# motoko_ice_dragon.net
KiCad netlist of a schematic drawn in EAGLE
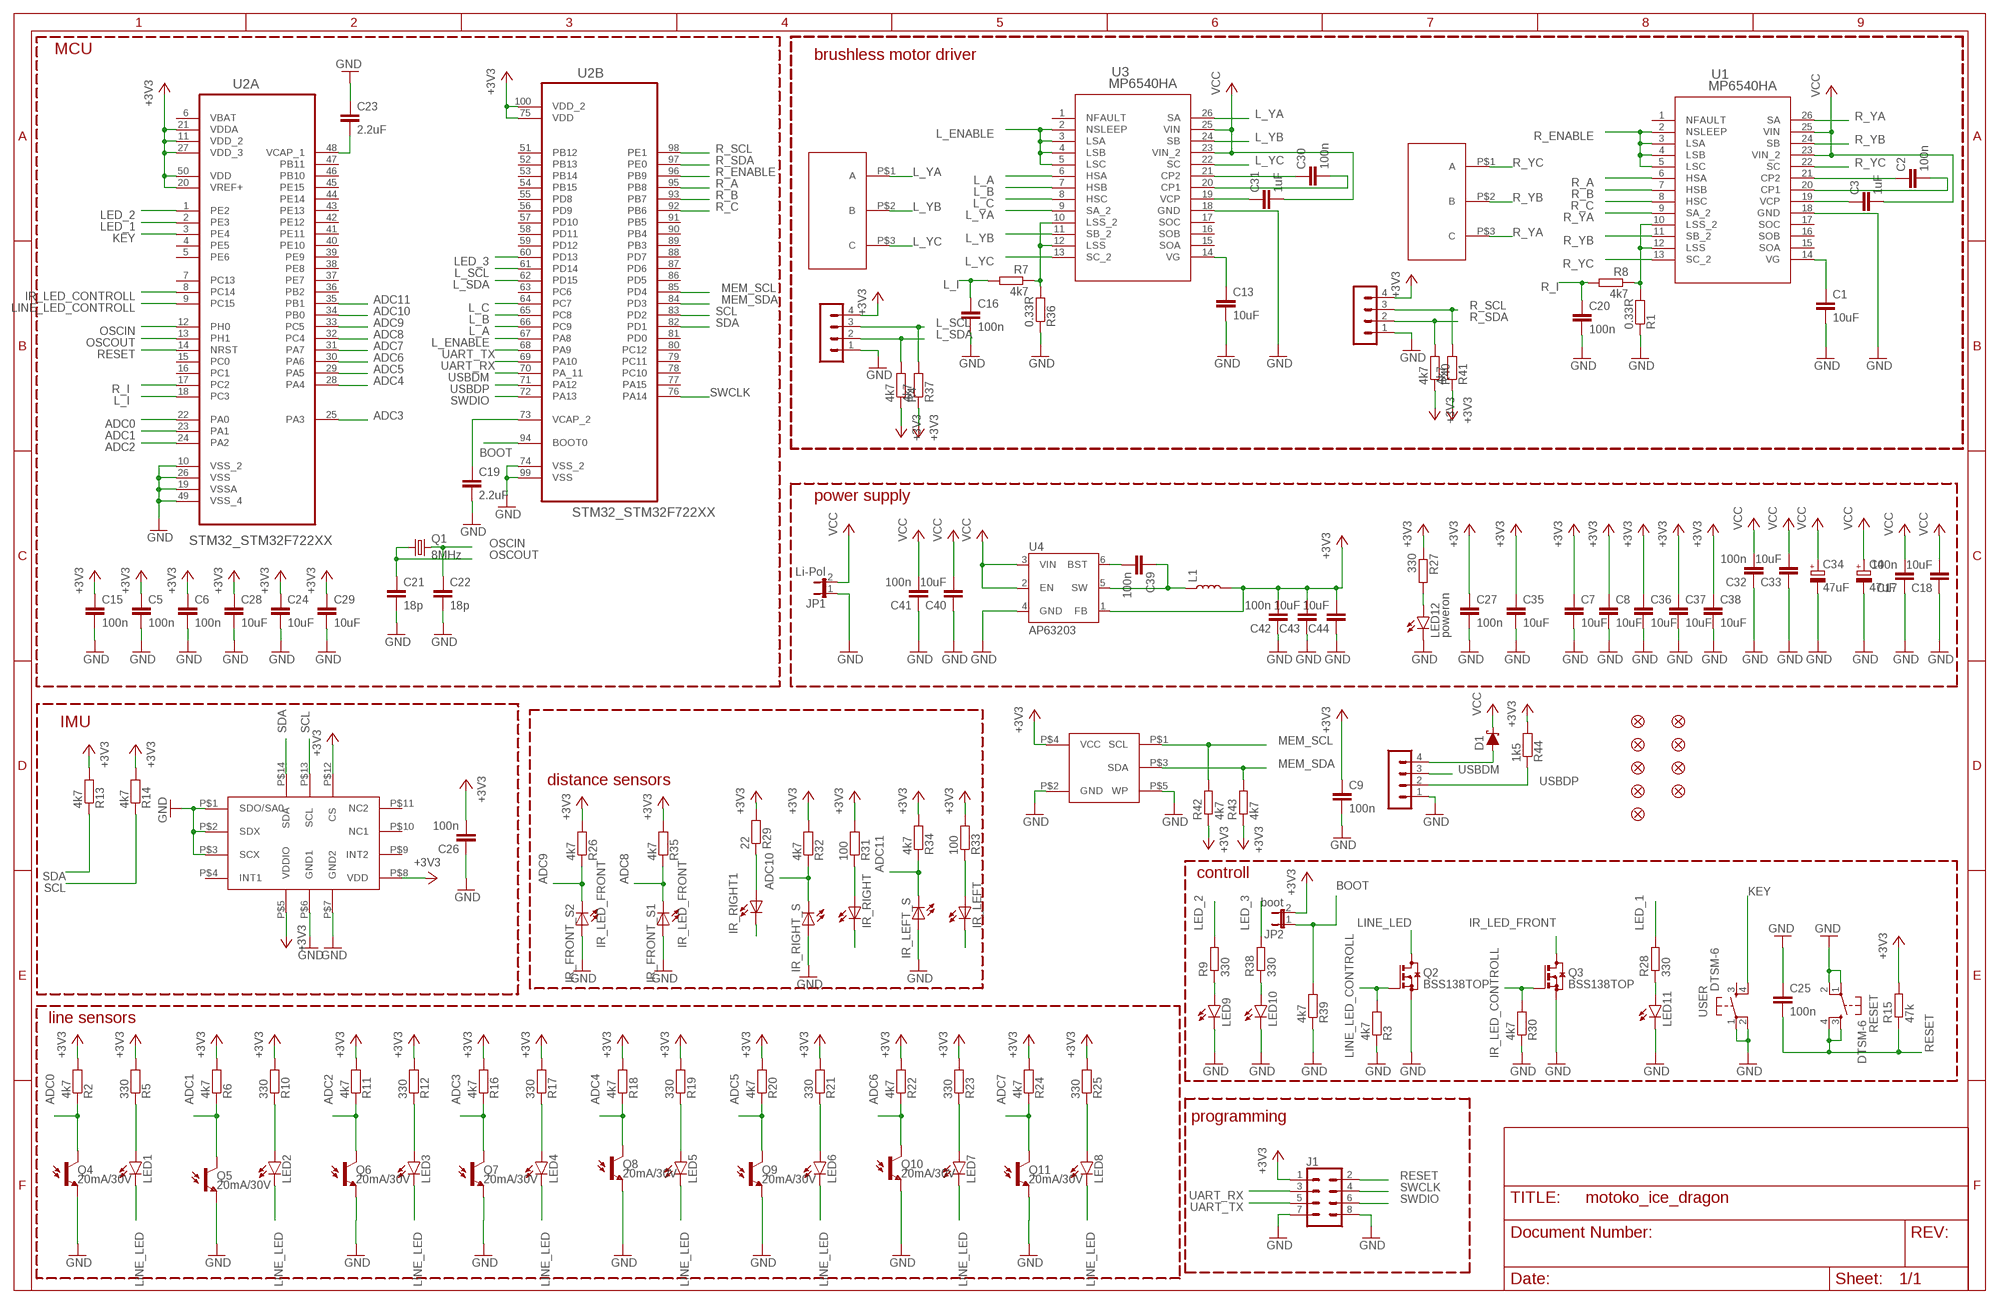
[diagram p0: schematic, sheet 1]

(export (version "E")
  (design (tool "Eeschema 10.0.6"))
  (components
    (comp (ref "C1")
      (value "10uF")
      (footprint "eagle-import:C0805")
      (libsource (lib "eagle-import") (part "C-EUC0805"))
    )
    (comp (ref "C2")
      (value "100n")
      (footprint "eagle-import:C0805")
      (libsource (lib "eagle-import") (part "C-EUC0805"))
    )
    (comp (ref "C3")
      (value "1uF")
      (footprint "eagle-import:C0805")
      (libsource (lib "eagle-import") (part "C-EUC0805"))
    )
    (comp (ref "C4")
      (value "47uF")
      (footprint "eagle-import:140CLH-1010")
      (libsource (lib "eagle-import") (part "CPOL-EU140CLH-1010"))
    )
    (comp (ref "C5")
      (value "100n")
      (footprint "eagle-import:C0805")
      (libsource (lib "eagle-import") (part "C-EUC0805"))
    )
    (comp (ref "C6")
      (value "100n")
      (footprint "eagle-import:C0805")
      (libsource (lib "eagle-import") (part "C-EUC0805"))
    )
    (comp (ref "C7")
      (value "10uF")
      (footprint "eagle-import:C0805")
      (libsource (lib "eagle-import") (part "C-EUC0805"))
    )
    (comp (ref "C8")
      (value "10uF")
      (footprint "eagle-import:C0805")
      (libsource (lib "eagle-import") (part "C-EUC0805"))
    )
    (comp (ref "C9")
      (value "100n")
      (footprint "eagle-import:C0805")
      (libsource (lib "eagle-import") (part "C-EUC0805"))
    )
    (comp (ref "C13")
      (value "10uF")
      (footprint "eagle-import:C0805")
      (libsource (lib "eagle-import") (part "C-EUC0805"))
    )
    (comp (ref "C15")
      (value "100n")
      (footprint "eagle-import:C0805")
      (libsource (lib "eagle-import") (part "C-EUC0805"))
    )
    (comp (ref "C16")
      (value "100n")
      (footprint "eagle-import:C0805")
      (libsource (lib "eagle-import") (part "C-EUC0805"))
    )
    (comp (ref "C17")
      (value "100n")
      (footprint "eagle-import:C0805")
      (libsource (lib "eagle-import") (part "C-EUC0805"))
    )
    (comp (ref "C18")
      (value "10uF")
      (footprint "eagle-import:C0805")
      (libsource (lib "eagle-import") (part "C-EUC0805"))
    )
    (comp (ref "C19")
      (value "2.2uF")
      (footprint "eagle-import:C0805")
      (libsource (lib "eagle-import") (part "C-EUC0805"))
    )
    (comp (ref "C20")
      (value "100n")
      (footprint "eagle-import:C0805")
      (libsource (lib "eagle-import") (part "C-EUC0805"))
    )
    (comp (ref "C21")
      (value "18p")
      (footprint "eagle-import:C0805")
      (libsource (lib "eagle-import") (part "C-EUC0805"))
    )
    (comp (ref "C22")
      (value "18p")
      (footprint "eagle-import:C0805")
      (libsource (lib "eagle-import") (part "C-EUC0805"))
    )
    (comp (ref "C23")
      (value "2.2uF")
      (footprint "eagle-import:C0805")
      (libsource (lib "eagle-import") (part "C-EUC0805"))
    )
    (comp (ref "C24")
      (value "10uF")
      (footprint "eagle-import:C0805")
      (libsource (lib "eagle-import") (part "C-EUC0805"))
    )
    (comp (ref "C25")
      (value "100n")
      (footprint "eagle-import:C0805")
      (libsource (lib "eagle-import") (part "C-EUC0805"))
    )
    (comp (ref "C26")
      (value "100n")
      (footprint "eagle-import:C0805")
      (libsource (lib "eagle-import") (part "C-EUC0805"))
    )
    (comp (ref "C27")
      (value "100n")
      (footprint "eagle-import:C0805")
      (libsource (lib "eagle-import") (part "C-EUC0805"))
    )
    (comp (ref "C28")
      (value "10uF")
      (footprint "eagle-import:C0805")
      (libsource (lib "eagle-import") (part "C-EUC0805"))
    )
    (comp (ref "C29")
      (value "10uF")
      (footprint "eagle-import:C0805")
      (libsource (lib "eagle-import") (part "C-EUC0805"))
    )
    (comp (ref "C30")
      (value "100n")
      (footprint "eagle-import:C0805")
      (libsource (lib "eagle-import") (part "C-EUC0805"))
    )
    (comp (ref "C31")
      (value "1uF")
      (footprint "eagle-import:C0805")
      (libsource (lib "eagle-import") (part "C-EUC0805"))
    )
    (comp (ref "C32")
      (value "100n")
      (footprint "eagle-import:C0805")
      (libsource (lib "eagle-import") (part "C-EUC0805"))
    )
    (comp (ref "C33")
      (value "10uF")
      (footprint "eagle-import:C0805")
      (libsource (lib "eagle-import") (part "C-EUC0805"))
    )
    (comp (ref "C34")
      (value "47uF")
      (footprint "eagle-import:140CLH-1010")
      (libsource (lib "eagle-import") (part "CPOL-EU140CLH-1010"))
    )
    (comp (ref "C35")
      (value "10uF")
      (footprint "eagle-import:C0805")
      (libsource (lib "eagle-import") (part "C-EUC0805"))
    )
    (comp (ref "C36")
      (value "10uF")
      (footprint "eagle-import:C0805")
      (libsource (lib "eagle-import") (part "C-EUC0805"))
    )
    (comp (ref "C37")
      (value "10uF")
      (footprint "eagle-import:C0805")
      (libsource (lib "eagle-import") (part "C-EUC0805"))
    )
    (comp (ref "C38")
      (value "10uF")
      (footprint "eagle-import:C0805")
      (libsource (lib "eagle-import") (part "C-EUC0805"))
    )
    (comp (ref "C39")
      (value "100n")
      (footprint "eagle-import:C0805")
      (libsource (lib "eagle-import") (part "C-EUC0805"))
    )
    (comp (ref "C40")
      (value "10uF")
      (footprint "eagle-import:C0805")
      (libsource (lib "eagle-import") (part "C-EUC0805"))
    )
    (comp (ref "C41")
      (value "100n")
      (footprint "eagle-import:C0805")
      (libsource (lib "eagle-import") (part "C-EUC0805"))
    )
    (comp (ref "C42")
      (value "100n")
      (footprint "eagle-import:C0805")
      (libsource (lib "eagle-import") (part "C-EUC0805"))
    )
    (comp (ref "C43")
      (value "10uF")
      (footprint "eagle-import:C0805")
      (libsource (lib "eagle-import") (part "C-EUC0805"))
    )
    (comp (ref "C44")
      (value "10uF")
      (footprint "eagle-import:C0805")
      (libsource (lib "eagle-import") (part "C-EUC0805"))
    )
    (comp (ref "D1")
      (value "3A/40V/500mV")
      (footprint "eagle-import:SMA-DIODE")
      (libsource (lib "eagle-import") (part "DIODE-SCHOTTKY-B340A"))
    )
    (comp (ref "FD1")
      (value "FIDUCIAL1X2")
      (footprint "eagle-import:FIDUCIAL-1X2")
      (libsource (lib "eagle-import") (part "FIDUCIAL1X2"))
    )
    (comp (ref "FD2")
      (value "FIDUCIAL1X2")
      (footprint "eagle-import:FIDUCIAL-1X2")
      (libsource (lib "eagle-import") (part "FIDUCIAL1X2"))
    )
    (comp (ref "FD3")
      (value "FIDUCIAL1X2")
      (footprint "eagle-import:FIDUCIAL-1X2")
      (libsource (lib "eagle-import") (part "FIDUCIAL1X2"))
    )
    (comp (ref "FD4")
      (value "FIDUCIAL1X2")
      (footprint "eagle-import:FIDUCIAL-1X2")
      (libsource (lib "eagle-import") (part "FIDUCIAL1X2"))
    )
    (comp (ref "FD5")
      (value "FIDUCIAL1X2")
      (footprint "eagle-import:FIDUCIAL-1X2")
      (libsource (lib "eagle-import") (part "FIDUCIAL1X2"))
    )
    (comp (ref "FD6")
      (value "FIDUCIAL1X2")
      (footprint "eagle-import:FIDUCIAL-1X2")
      (libsource (lib "eagle-import") (part "FIDUCIAL1X2"))
    )
    (comp (ref "FD7")
      (value "FIDUCIAL1X2")
      (footprint "eagle-import:FIDUCIAL-1X2")
      (libsource (lib "eagle-import") (part "FIDUCIAL1X2"))
    )
    (comp (ref "FD8")
      (value "FIDUCIAL1X2")
      (footprint "eagle-import:FIDUCIAL-1X2")
      (libsource (lib "eagle-import") (part "FIDUCIAL1X2"))
    )
    (comp (ref "FD9")
      (value "FIDUCIAL1X2")
      (footprint "eagle-import:FIDUCIAL-1X2")
      (libsource (lib "eagle-import") (part "FIDUCIAL1X2"))
    )
    (comp (ref "IR_FRONT_S1")
      (value "LED5MM")
      (footprint "eagle-import:LED5MM")
      (libsource (lib "eagle-import") (part "my_parts_LED5MM"))
    )
    (comp (ref "IR_FRONT_S2")
      (value "LED5MM")
      (footprint "eagle-import:LED5MM")
      (libsource (lib "eagle-import") (part "my_parts_LED5MM"))
    )
    (comp (ref "IR_LEFT")
      (value "LED5MM")
      (footprint "eagle-import:LED5MM")
      (libsource (lib "eagle-import") (part "my_parts_LED5MM"))
    )
    (comp (ref "IR_LEFT_S")
      (value "LED5MM")
      (footprint "eagle-import:LED5MM")
      (libsource (lib "eagle-import") (part "my_parts_LED5MM"))
    )
    (comp (ref "IR_RIGHT")
      (value "LED5MM")
      (footprint "eagle-import:LED5MM")
      (libsource (lib "eagle-import") (part "my_parts_LED5MM"))
    )
    (comp (ref "IR_RIGHT1")
      (value "LED5MM")
      (footprint "eagle-import:LED5MM")
      (libsource (lib "eagle-import") (part "my_parts_LED5MM"))
    )
    (comp (ref "IR_RIGHT_S")
      (value "LED5MM")
      (footprint "eagle-import:LED5MM")
      (libsource (lib "eagle-import") (part "my_parts_LED5MM"))
    )
    (comp (ref "J1")
      (value "CONN_04X2")
      (footprint "eagle-import:2X4")
      (libsource (lib "eagle-import") (part "CONN_04X2"))
    )
    (comp (ref "JP1")
      (value "Li-Pol")
      (footprint "eagle-import:JP1")
      (libsource (lib "eagle-import") (part "JP1E"))
    )
    (comp (ref "JP2")
      (value "boot")
      (footprint "eagle-import:JP1")
      (libsource (lib "eagle-import") (part "JP1E"))
    )
    (comp (ref "L1")
      (value "4.7uH, TYS50204R7N-10")
      (footprint "eagle-import:CR54")
      (libsource (lib "eagle-import") (part "INDUCTOR-CR54-3.3UH"))
    )
    (comp (ref "LED1")
      (value "LEDCHIPLED_1206")
      (footprint "eagle-import:CHIPLED_1206")
      (libsource (lib "eagle-import") (part "LEDCHIPLED_1206"))
    )
    (comp (ref "LED2")
      (value "LEDCHIPLED_1206")
      (footprint "eagle-import:CHIPLED_1206")
      (libsource (lib "eagle-import") (part "LEDCHIPLED_1206"))
    )
    (comp (ref "LED3")
      (value "LEDCHIPLED_1206")
      (footprint "eagle-import:CHIPLED_1206")
      (libsource (lib "eagle-import") (part "LEDCHIPLED_1206"))
    )
    (comp (ref "LED4")
      (value "LEDCHIPLED_1206")
      (footprint "eagle-import:CHIPLED_1206")
      (libsource (lib "eagle-import") (part "LEDCHIPLED_1206"))
    )
    (comp (ref "LED5")
      (value "LEDCHIPLED_1206")
      (footprint "eagle-import:CHIPLED_1206")
      (libsource (lib "eagle-import") (part "LEDCHIPLED_1206"))
    )
    (comp (ref "LED6")
      (value "LEDCHIPLED_1206")
      (footprint "eagle-import:CHIPLED_1206")
      (libsource (lib "eagle-import") (part "LEDCHIPLED_1206"))
    )
    (comp (ref "LED7")
      (value "LEDCHIPLED_1206")
      (footprint "eagle-import:CHIPLED_1206")
      (libsource (lib "eagle-import") (part "LEDCHIPLED_1206"))
    )
    (comp (ref "LED8")
      (value "LEDCHIPLED_1206")
      (footprint "eagle-import:CHIPLED_1206")
      (libsource (lib "eagle-import") (part "LEDCHIPLED_1206"))
    )
    (comp (ref "LED9")
      (value "LEDCHIPLED_1206")
      (footprint "eagle-import:CHIPLED_1206")
      (libsource (lib "eagle-import") (part "LEDCHIPLED_1206"))
    )
    (comp (ref "LED10")
      (value "LEDCHIPLED_1206")
      (footprint "eagle-import:CHIPLED_1206")
      (libsource (lib "eagle-import") (part "LEDCHIPLED_1206"))
    )
    (comp (ref "LED11")
      (value "LEDCHIPLED_1206")
      (footprint "eagle-import:CHIPLED_1206")
      (libsource (lib "eagle-import") (part "LEDCHIPLED_1206"))
    )
    (comp (ref "LED12")
      (value "poweron")
      (footprint "eagle-import:CHIPLED_1206")
      (libsource (lib "eagle-import") (part "LEDCHIPLED_1206"))
    )
    (comp (ref "L_ENCODER")
      (value "MA04-1")
      (footprint "eagle-import:MA04-1")
      (libsource (lib "eagle-import") (part "MA04-1"))
    )
    (comp (ref "L_ENCODER1")
      (value "MA04-1")
      (footprint "eagle-import:MA04-1")
      (libsource (lib "eagle-import") (part "MA04-1"))
    )
    (comp (ref "L_ENCODER2")
      (value "MA04-1")
      (footprint "eagle-import:MA04-1")
      (libsource (lib "eagle-import") (part "MA04-1"))
    )
    (comp (ref "Q1")
      (value "8MHz")
      (footprint "eagle-import:CTS406")
      (libsource (lib "eagle-import") (part "CRYSTALCTS406"))
    )
    (comp (ref "Q2")
      (value "BSS138TOP")
      (footprint "eagle-import:SOT23")
      (libsource (lib "eagle-import") (part "BSS138TOP"))
    )
    (comp (ref "Q3")
      (value "BSS138TOP")
      (footprint "eagle-import:SOT23")
      (libsource (lib "eagle-import") (part "BSS138TOP"))
    )
    (comp (ref "Q4")
      (value "20mA/30V")
      (footprint "eagle-import:PT17-21C-L41-TR8")
      (libsource (lib "eagle-import") (part "PHOTOTRANSISTORPT17-21C-L41-TR8"))
    )
    (comp (ref "Q5")
      (value "20mA/30V")
      (footprint "eagle-import:PT17-21C-L41-TR8")
      (libsource (lib "eagle-import") (part "PHOTOTRANSISTORPT17-21C-L41-TR8"))
    )
    (comp (ref "Q6")
      (value "20mA/30V")
      (footprint "eagle-import:PT17-21C-L41-TR8")
      (libsource (lib "eagle-import") (part "PHOTOTRANSISTORPT17-21C-L41-TR8"))
    )
    (comp (ref "Q7")
      (value "20mA/30V")
      (footprint "eagle-import:PT17-21C-L41-TR8")
      (libsource (lib "eagle-import") (part "PHOTOTRANSISTORPT17-21C-L41-TR8"))
    )
    (comp (ref "Q8")
      (value "20mA/30V")
      (footprint "eagle-import:PT17-21C-L41-TR8")
      (libsource (lib "eagle-import") (part "PHOTOTRANSISTORPT17-21C-L41-TR8"))
    )
    (comp (ref "Q9")
      (value "20mA/30V")
      (footprint "eagle-import:PT17-21C-L41-TR8")
      (libsource (lib "eagle-import") (part "PHOTOTRANSISTORPT17-21C-L41-TR8"))
    )
    (comp (ref "Q10")
      (value "20mA/30V")
      (footprint "eagle-import:PT17-21C-L41-TR8")
      (libsource (lib "eagle-import") (part "PHOTOTRANSISTORPT17-21C-L41-TR8"))
    )
    (comp (ref "Q11")
      (value "20mA/30V")
      (footprint "eagle-import:PT17-21C-L41-TR8")
      (libsource (lib "eagle-import") (part "PHOTOTRANSISTORPT17-21C-L41-TR8"))
    )
    (comp (ref "R1")
      (value "0.33R")
      (footprint "eagle-import:M1206")
      (libsource (lib "eagle-import") (part "R-EU_M1206"))
    )
    (comp (ref "R2")
      (value "4k7")
      (footprint "eagle-import:M0805")
      (libsource (lib "eagle-import") (part "resistor_348_R-EU_M0805"))
    )
    (comp (ref "R3")
      (value "4k7")
      (footprint "eagle-import:M0805")
      (libsource (lib "eagle-import") (part "resistor_348_R-EU_M0805"))
    )
    (comp (ref "R4")
      (value "4k7")
      (footprint "eagle-import:M0805")
      (libsource (lib "eagle-import") (part "resistor_348_R-EU_M0805"))
    )
    (comp (ref "R5")
      (value "330")
      (footprint "eagle-import:M0805")
      (libsource (lib "eagle-import") (part "resistor_348_R-EU_M0805"))
    )
    (comp (ref "R6")
      (value "4k7")
      (footprint "eagle-import:M0805")
      (libsource (lib "eagle-import") (part "resistor_348_R-EU_M0805"))
    )
    (comp (ref "R7")
      (value "4k7")
      (footprint "eagle-import:M0805")
      (libsource (lib "eagle-import") (part "resistor_348_R-EU_M0805"))
    )
    (comp (ref "R8")
      (value "4k7")
      (footprint "eagle-import:M0805")
      (libsource (lib "eagle-import") (part "resistor_348_R-EU_M0805"))
    )
    (comp (ref "R9")
      (value "330")
      (footprint "eagle-import:M0805")
      (libsource (lib "eagle-import") (part "resistor_348_R-EU_M0805"))
    )
    (comp (ref "R10")
      (value "330")
      (footprint "eagle-import:M0805")
      (libsource (lib "eagle-import") (part "resistor_348_R-EU_M0805"))
    )
    (comp (ref "R11")
      (value "4k7")
      (footprint "eagle-import:M0805")
      (libsource (lib "eagle-import") (part "resistor_348_R-EU_M0805"))
    )
    (comp (ref "R12")
      (value "330")
      (footprint "eagle-import:M0805")
      (libsource (lib "eagle-import") (part "resistor_348_R-EU_M0805"))
    )
    (comp (ref "R13")
      (value "4k7")
      (footprint "eagle-import:M0805")
      (libsource (lib "eagle-import") (part "resistor_348_R-EU_M0805"))
    )
    (comp (ref "R14")
      (value "4k7")
      (footprint "eagle-import:M0805")
      (libsource (lib "eagle-import") (part "resistor_348_R-EU_M0805"))
    )
    (comp (ref "R15")
      (value "47k")
      (footprint "eagle-import:M0805")
      (libsource (lib "eagle-import") (part "resistor_348_R-EU_M0805"))
    )
    (comp (ref "R16")
      (value "4k7")
      (footprint "eagle-import:M0805")
      (libsource (lib "eagle-import") (part "resistor_348_R-EU_M0805"))
    )
    (comp (ref "R17")
      (value "330")
      (footprint "eagle-import:M0805")
      (libsource (lib "eagle-import") (part "resistor_348_R-EU_M0805"))
    )
    (comp (ref "R18")
      (value "4k7")
      (footprint "eagle-import:M0805")
      (libsource (lib "eagle-import") (part "resistor_348_R-EU_M0805"))
    )
    (comp (ref "R19")
      (value "330")
      (footprint "eagle-import:M0805")
      (libsource (lib "eagle-import") (part "resistor_348_R-EU_M0805"))
    )
    (comp (ref "R20")
      (value "4k7")
      (footprint "eagle-import:M0805")
      (libsource (lib "eagle-import") (part "resistor_348_R-EU_M0805"))
    )
    (comp (ref "R21")
      (value "330")
      (footprint "eagle-import:M0805")
      (libsource (lib "eagle-import") (part "resistor_348_R-EU_M0805"))
    )
    (comp (ref "R22")
      (value "4k7")
      (footprint "eagle-import:M0805")
      (libsource (lib "eagle-import") (part "resistor_348_R-EU_M0805"))
    )
    (comp (ref "R23")
      (value "330")
      (footprint "eagle-import:M0805")
      (libsource (lib "eagle-import") (part "resistor_348_R-EU_M0805"))
    )
    (comp (ref "R24")
      (value "4k7")
      (footprint "eagle-import:M0805")
      (libsource (lib "eagle-import") (part "resistor_348_R-EU_M0805"))
    )
    (comp (ref "R25")
      (value "330")
      (footprint "eagle-import:M0805")
      (libsource (lib "eagle-import") (part "resistor_348_R-EU_M0805"))
    )
    (comp (ref "R26")
      (value "4k7")
      (footprint "eagle-import:M0805")
      (libsource (lib "eagle-import") (part "resistor_348_R-EU_M0805"))
    )
    (comp (ref "R27")
      (value "330")
      (footprint "eagle-import:M0805")
      (libsource (lib "eagle-import") (part "resistor_348_R-EU_M0805"))
    )
    (comp (ref "R28")
      (value "330")
      (footprint "eagle-import:M0805")
      (libsource (lib "eagle-import") (part "resistor_348_R-EU_M0805"))
    )
    (comp (ref "R29")
      (value "22")
      (footprint "eagle-import:M0805")
      (libsource (lib "eagle-import") (part "resistor_348_R-EU_M0805"))
    )
    (comp (ref "R30")
      (value "4k7")
      (footprint "eagle-import:M0805")
      (libsource (lib "eagle-import") (part "resistor_348_R-EU_M0805"))
    )
    (comp (ref "R31")
      (value "100")
      (footprint "eagle-import:M0805")
      (libsource (lib "eagle-import") (part "resistor_348_R-EU_M0805"))
    )
    (comp (ref "R32")
      (value "4k7")
      (footprint "eagle-import:M0805")
      (libsource (lib "eagle-import") (part "resistor_348_R-EU_M0805"))
    )
    (comp (ref "R33")
      (value "100")
      (footprint "eagle-import:M0805")
      (libsource (lib "eagle-import") (part "resistor_348_R-EU_M0805"))
    )
    (comp (ref "R34")
      (value "4k7")
      (footprint "eagle-import:M0805")
      (libsource (lib "eagle-import") (part "resistor_348_R-EU_M0805"))
    )
    (comp (ref "R35")
      (value "4k7")
      (footprint "eagle-import:M0805")
      (libsource (lib "eagle-import") (part "resistor_348_R-EU_M0805"))
    )
    (comp (ref "R36")
      (value "0.33R")
      (footprint "eagle-import:M1206")
      (libsource (lib "eagle-import") (part "R-EU_M1206"))
    )
    (comp (ref "R37")
      (value "4k7")
      (footprint "eagle-import:M0805")
      (libsource (lib "eagle-import") (part "resistor_348_R-EU_M0805"))
    )
    (comp (ref "R38")
      (value "330")
      (footprint "eagle-import:M0805")
      (libsource (lib "eagle-import") (part "resistor_348_R-EU_M0805"))
    )
    (comp (ref "R39")
      (value "4k7")
      (footprint "eagle-import:M0805")
      (libsource (lib "eagle-import") (part "resistor_348_R-EU_M0805"))
    )
    (comp (ref "R40")
      (value "4k7")
      (footprint "eagle-import:M0805")
      (libsource (lib "eagle-import") (part "resistor_348_R-EU_M0805"))
    )
    (comp (ref "R41")
      (value "4k7")
      (footprint "eagle-import:M0805")
      (libsource (lib "eagle-import") (part "resistor_348_R-EU_M0805"))
    )
    (comp (ref "R42")
      (value "4k7")
      (footprint "eagle-import:M0805")
      (libsource (lib "eagle-import") (part "R-EU_M0805"))
    )
    (comp (ref "R43")
      (value "4k7")
      (footprint "eagle-import:M0805")
      (libsource (lib "eagle-import") (part "R-EU_M0805"))
    )
    (comp (ref "R44")
      (value "1k5")
      (footprint "eagle-import:M0805")
      (libsource (lib "eagle-import") (part "resistor_348_R-EU_M0805"))
    )
    (comp (ref "RESET")
      (value "DTSM-6")
      (footprint "eagle-import:DTSM-6")
      (libsource (lib "eagle-import") (part "DTSM-6"))
    )
    (comp (ref "U$1")
      (value "BRUSHLESS_GIMBAL_MOTOR_WHEEL")
      (footprint "eagle-import:BRUSHLESS_GIMBAL_MOTOR_WHEEL")
      (libsource (lib "eagle-import") (part "BRUSHLESS_GIMBAL_MOTOR_WHEEL"))
    )
    (comp (ref "U$2")
      (value "BRUSHLESS_GIMBAL_MOTOR_WHEEL")
      (footprint "eagle-import:BRUSHLESS_GIMBAL_MOTOR_WHEEL")
      (libsource (lib "eagle-import") (part "BRUSHLESS_GIMBAL_MOTOR_WHEEL"))
    )
    (comp (ref "U$3")
      (value "LSM6DSM")
      (footprint "eagle-import:LGA14L")
      (libsource (lib "eagle-import") (part "LSM6DSM"))
    )
    (comp (ref "U$4")
      (value "24LC24_SOT23")
      (footprint "eagle-import:SOT23")
      (libsource (lib "eagle-import") (part "24LC24_SOT23"))
    )
    (comp (ref "U1")
      (value "MP6540HA")
      (footprint "eagle-import:QFN-5X5_MP6540HA_MNP")
      (fields (field (name "COPYRIGHT") "Copyright (C) 2018 Accelerated Designs. All rights reserved"))
      (libsource (lib "eagle-import") (part "MP6540HA"))
    )
    (comp (ref "U2")
      (value "STM32_STM32F722XX")
      (footprint "eagle-import:STM32_QFP50P1600X1600X160-100N")
      (fields (field (name "MPN") "STM32F407VET6"))
      (libsource (lib "eagle-import") (part "STM32_STM32F722XX"))
    )
    (comp (ref "U3")
      (value "MP6540HA")
      (footprint "eagle-import:QFN-5X5_MP6540HA_MNP")
      (fields (field (name "COPYRIGHT") "Copyright (C) 2018 Accelerated Designs. All rights reserved"))
      (libsource (lib "eagle-import") (part "MP6540HA"))
    )
    (comp (ref "U4")
      (value "AP63203")
      (footprint "eagle-import:SOT23-6")
      (libsource (lib "eagle-import") (part "AP63203"))
    )
    (comp (ref "USER")
      (value "DTSM-6")
      (footprint "eagle-import:DTSM-6")
      (libsource (lib "eagle-import") (part "DTSM-6"))
    )
  )
  (nets
    (net (code "1") (name "+3V3") (class "Default")
      (node (ref "C15") (pin "1") (pinfunction "1_1") (pintype "passive"))
      (node (ref "C24") (pin "1") (pinfunction "1_1") (pintype "passive"))
      (node (ref "C26") (pin "2") (pinfunction "2_2") (pintype "passive"))
      (node (ref "C27") (pin "1") (pinfunction "1_1") (pintype "passive"))
      (node (ref "C28") (pin "1") (pinfunction "1_1") (pintype "passive"))
      (node (ref "C29") (pin "1") (pinfunction "1_1") (pintype "passive"))
      (node (ref "C35") (pin "1") (pinfunction "1_1") (pintype "passive"))
      (node (ref "C36") (pin "1") (pinfunction "1_1") (pintype "passive"))
      (node (ref "C37") (pin "1") (pinfunction "1_1") (pintype "passive"))
      (node (ref "C38") (pin "1") (pinfunction "1_1") (pintype "passive"))
      (node (ref "C42") (pin "2") (pinfunction "2_2") (pintype "passive"))
      (node (ref "C43") (pin "2") (pinfunction "2_2") (pintype "passive"))
      (node (ref "C44") (pin "2") (pinfunction "2_2") (pintype "passive"))
      (node (ref "C5") (pin "1") (pinfunction "1_1") (pintype "passive"))
      (node (ref "C6") (pin "1") (pinfunction "1_1") (pintype "passive"))
      (node (ref "C7") (pin "1") (pinfunction "1_1") (pintype "passive"))
      (node (ref "C8") (pin "1") (pinfunction "1_1") (pintype "passive"))
      (node (ref "C9") (pin "1") (pinfunction "1_1") (pintype "passive"))
      (node (ref "J1") (pin "1") (pinfunction "1_1") (pintype "passive"))
      (node (ref "JP2") (pin "2") (pinfunction "2_2") (pintype "passive"))
      (node (ref "L1") (pin "P$2") (pinfunction "2_P$2") (pintype "passive"))
      (node (ref "L_ENCODER") (pin "4") (pinfunction "4_4") (pintype "passive"))
      (node (ref "L_ENCODER1") (pin "4") (pinfunction "4_4") (pintype "passive"))
      (node (ref "R10") (pin "2") (pinfunction "2_2") (pintype "passive"))
      (node (ref "R11") (pin "2") (pinfunction "2_2") (pintype "passive"))
      (node (ref "R12") (pin "2") (pinfunction "2_2") (pintype "passive"))
      (node (ref "R13") (pin "2") (pinfunction "2_2") (pintype "passive"))
      (node (ref "R14") (pin "2") (pinfunction "2_2") (pintype "passive"))
      (node (ref "R15") (pin "2") (pinfunction "2_2") (pintype "passive"))
      (node (ref "R16") (pin "2") (pinfunction "2_2") (pintype "passive"))
      (node (ref "R17") (pin "2") (pinfunction "2_2") (pintype "passive"))
      (node (ref "R18") (pin "2") (pinfunction "2_2") (pintype "passive"))
      (node (ref "R19") (pin "2") (pinfunction "2_2") (pintype "passive"))
      (node (ref "R2") (pin "2") (pinfunction "2_2") (pintype "passive"))
      (node (ref "R20") (pin "2") (pinfunction "2_2") (pintype "passive"))
      (node (ref "R21") (pin "2") (pinfunction "2_2") (pintype "passive"))
      (node (ref "R22") (pin "2") (pinfunction "2_2") (pintype "passive"))
      (node (ref "R23") (pin "2") (pinfunction "2_2") (pintype "passive"))
      (node (ref "R24") (pin "2") (pinfunction "2_2") (pintype "passive"))
      (node (ref "R25") (pin "2") (pinfunction "2_2") (pintype "passive"))
      (node (ref "R26") (pin "2") (pinfunction "2_2") (pintype "passive"))
      (node (ref "R27") (pin "1") (pinfunction "1_1") (pintype "passive"))
      (node (ref "R29") (pin "2") (pinfunction "2_2") (pintype "passive"))
      (node (ref "R31") (pin "2") (pinfunction "2_2") (pintype "passive"))
      (node (ref "R32") (pin "2") (pinfunction "2_2") (pintype "passive"))
      (node (ref "R33") (pin "2") (pinfunction "2_2") (pintype "passive"))
      (node (ref "R34") (pin "2") (pinfunction "2_2") (pintype "passive"))
      (node (ref "R35") (pin "2") (pinfunction "2_2") (pintype "passive"))
      (node (ref "R37") (pin "1") (pinfunction "1_1") (pintype "passive"))
      (node (ref "R4") (pin "1") (pinfunction "1_1") (pintype "passive"))
      (node (ref "R40") (pin "1") (pinfunction "1_1") (pintype "passive"))
      (node (ref "R41") (pin "1") (pinfunction "1_1") (pintype "passive"))
      (node (ref "R42") (pin "1") (pinfunction "1_1") (pintype "passive"))
      (node (ref "R43") (pin "1") (pinfunction "1_1") (pintype "passive"))
      (node (ref "R44") (pin "2") (pinfunction "2_2") (pintype "passive"))
      (node (ref "R5") (pin "2") (pinfunction "2_2") (pintype "passive"))
      (node (ref "R6") (pin "2") (pinfunction "2_2") (pintype "passive"))
      (node (ref "U$3") (pin "P$12") (pinfunction "CS_P$12") (pintype "bidirectional"))
      (node (ref "U$3") (pin "P$5") (pinfunction "VDDIO_P$5") (pintype "bidirectional"))
      (node (ref "U$3") (pin "P$8") (pinfunction "VDD_P$8") (pintype "bidirectional"))
      (node (ref "U$4") (pin "P$4") (pinfunction "VCC_P$4") (pintype "bidirectional"))
      (node (ref "U2") (pin "100") (pinfunction "VDD_2_100") (pintype "power_in"))
      (node (ref "U2") (pin "11") (pinfunction "VDD_2_11") (pintype "power_in"))
      (node (ref "U2") (pin "20") (pinfunction "VREF+_20") (pintype "power_in"))
      (node (ref "U2") (pin "21") (pinfunction "VDDA_21") (pintype "power_in"))
      (node (ref "U2") (pin "27") (pinfunction "VDD_3_27") (pintype "power_in"))
      (node (ref "U2") (pin "50") (pinfunction "VDD_50") (pintype "power_in"))
      (node (ref "U2") (pin "75") (pinfunction "VDD_75") (pintype "power_in"))
      (node (ref "U4") (pin "1") (pinfunction "FB_1") (pintype "bidirectional"))
    )
    (net (code "2") (name "/ADC0") (class "Default")
      (node (ref "Q4") (pin "C") (pinfunction "C_C") (pintype "passive"))
      (node (ref "R2") (pin "1") (pinfunction "1_1") (pintype "passive"))
      (node (ref "U2") (pin "22") (pinfunction "PA0_22") (pintype "bidirectional"))
    )
    (net (code "3") (name "/ADC1") (class "Default")
      (node (ref "Q5") (pin "C") (pinfunction "C_C") (pintype "passive"))
      (node (ref "R6") (pin "1") (pinfunction "1_1") (pintype "passive"))
      (node (ref "U2") (pin "23") (pinfunction "PA1_23") (pintype "bidirectional"))
    )
    (net (code "4") (name "/ADC2") (class "Default")
      (node (ref "Q6") (pin "C") (pinfunction "C_C") (pintype "passive"))
      (node (ref "R11") (pin "1") (pinfunction "1_1") (pintype "passive"))
      (node (ref "U2") (pin "24") (pinfunction "PA2_24") (pintype "bidirectional"))
    )
    (net (code "5") (name "/ADC3") (class "Default")
      (node (ref "Q7") (pin "C") (pinfunction "C_C") (pintype "passive"))
      (node (ref "R16") (pin "1") (pinfunction "1_1") (pintype "passive"))
      (node (ref "U2") (pin "25") (pinfunction "PA3_25") (pintype "bidirectional"))
    )
    (net (code "6") (name "/ADC4") (class "Default")
      (node (ref "Q8") (pin "C") (pinfunction "C_C") (pintype "passive"))
      (node (ref "R18") (pin "1") (pinfunction "1_1") (pintype "passive"))
      (node (ref "U2") (pin "28") (pinfunction "PA4_28") (pintype "bidirectional"))
    )
    (net (code "7") (name "/ADC5") (class "Default")
      (node (ref "Q9") (pin "C") (pinfunction "C_C") (pintype "passive"))
      (node (ref "R20") (pin "1") (pinfunction "1_1") (pintype "passive"))
      (node (ref "U2") (pin "29") (pinfunction "PA5_29") (pintype "bidirectional"))
    )
    (net (code "8") (name "/ADC6") (class "Default")
      (node (ref "Q10") (pin "C") (pinfunction "C_C") (pintype "passive"))
      (node (ref "R22") (pin "1") (pinfunction "1_1") (pintype "passive"))
      (node (ref "U2") (pin "30") (pinfunction "PA6_30") (pintype "bidirectional"))
    )
    (net (code "9") (name "/ADC7") (class "Default")
      (node (ref "Q11") (pin "C") (pinfunction "C_C") (pintype "passive"))
      (node (ref "R24") (pin "1") (pinfunction "1_1") (pintype "passive"))
      (node (ref "U2") (pin "31") (pinfunction "PA7_31") (pintype "bidirectional"))
    )
    (net (code "10") (name "/ADC8") (class "Default")
      (node (ref "IR_FRONT_S1") (pin "K") (pinfunction "C_K") (pintype "passive"))
      (node (ref "R35") (pin "1") (pinfunction "1_1") (pintype "passive"))
      (node (ref "U2") (pin "32") (pinfunction "PC4_32") (pintype "bidirectional"))
    )
    (net (code "11") (name "/ADC9") (class "Default")
      (node (ref "IR_FRONT_S2") (pin "K") (pinfunction "C_K") (pintype "passive"))
      (node (ref "R26") (pin "1") (pinfunction "1_1") (pintype "passive"))
      (node (ref "U2") (pin "33") (pinfunction "PC5_33") (pintype "bidirectional"))
    )
    (net (code "12") (name "/ADC10") (class "Default")
      (node (ref "IR_RIGHT_S") (pin "K") (pinfunction "C_K") (pintype "passive"))
      (node (ref "R32") (pin "1") (pinfunction "1_1") (pintype "passive"))
      (node (ref "U2") (pin "34") (pinfunction "PB0_34") (pintype "bidirectional"))
    )
    (net (code "13") (name "/ADC11") (class "Default")
      (node (ref "IR_LEFT_S") (pin "K") (pinfunction "C_K") (pintype "passive"))
      (node (ref "R34") (pin "1") (pinfunction "1_1") (pintype "passive"))
      (node (ref "U2") (pin "35") (pinfunction "PB1_35") (pintype "bidirectional"))
    )
    (net (code "14") (name "/BOOT") (class "Default")
      (node (ref "JP2") (pin "1") (pinfunction "1_1") (pintype "passive"))
      (node (ref "R39") (pin "2") (pinfunction "2_2") (pintype "passive"))
      (node (ref "U2") (pin "94") (pinfunction "BOOT0_94") (pintype "input"))
    )
    (net (code "15") (name "/IR_LED_CONTROLL") (class "Default")
      (node (ref "Q3") (pin "1") (pinfunction "G_1") (pintype "passive"))
      (node (ref "R30") (pin "2") (pinfunction "2_2") (pintype "passive"))
      (node (ref "U2") (pin "8") (pinfunction "PC14_8") (pintype "bidirectional"))
    )
    (net (code "16") (name "/IR_LED_FRONT") (class "Default")
      (node (ref "IR_LEFT") (pin "K") (pinfunction "C_K") (pintype "passive"))
      (node (ref "IR_RIGHT") (pin "K") (pinfunction "C_K") (pintype "passive"))
      (node (ref "IR_RIGHT1") (pin "K") (pinfunction "C_K") (pintype "passive"))
      (node (ref "Q3") (pin "3") (pinfunction "D_3") (pintype "passive"))
    )
    (net (code "17") (name "/KEY") (class "Default")
      (node (ref "U2") (pin "3") (pinfunction "PE4_3") (pintype "bidirectional"))
      (node (ref "USER") (pin "4") (pinfunction "4_4") (pintype "passive"))
    )
    (net (code "18") (name "/LED_1") (class "Default")
      (node (ref "R28") (pin "2") (pinfunction "2_2") (pintype "passive"))
      (node (ref "U2") (pin "2") (pinfunction "PE3_2") (pintype "bidirectional"))
    )
    (net (code "19") (name "/LED_2") (class "Default")
      (node (ref "R9") (pin "2") (pinfunction "2_2") (pintype "passive"))
      (node (ref "U2") (pin "1") (pinfunction "PE2_1") (pintype "bidirectional"))
    )
    (net (code "20") (name "/LED_3") (class "Default")
      (node (ref "R38") (pin "2") (pinfunction "2_2") (pintype "passive"))
      (node (ref "U2") (pin "60") (pinfunction "PD13_60") (pintype "bidirectional"))
    )
    (net (code "21") (name "/LINE_LED") (class "Default")
      (node (ref "LED1") (pin "C") (pinfunction "C_C") (pintype "passive"))
      (node (ref "LED2") (pin "C") (pinfunction "C_C") (pintype "passive"))
      (node (ref "LED3") (pin "C") (pinfunction "C_C") (pintype "passive"))
      (node (ref "LED4") (pin "C") (pinfunction "C_C") (pintype "passive"))
      (node (ref "LED5") (pin "C") (pinfunction "C_C") (pintype "passive"))
      (node (ref "LED6") (pin "C") (pinfunction "C_C") (pintype "passive"))
      (node (ref "LED7") (pin "C") (pinfunction "C_C") (pintype "passive"))
      (node (ref "LED8") (pin "C") (pinfunction "C_C") (pintype "passive"))
      (node (ref "Q2") (pin "3") (pinfunction "D_3") (pintype "passive"))
    )
    (net (code "22") (name "/LINE_LED_CONTROLL") (class "Default")
      (node (ref "Q2") (pin "1") (pinfunction "G_1") (pintype "passive"))
      (node (ref "R3") (pin "2") (pinfunction "2_2") (pintype "passive"))
      (node (ref "U2") (pin "9") (pinfunction "PC15_9") (pintype "bidirectional"))
    )
    (net (code "23") (name "/L_A") (class "Default")
      (node (ref "U2") (pin "66") (pinfunction "PC9_66") (pintype "bidirectional"))
      (node (ref "U3") (pin "6") (pinfunction "HSA_6") (pintype "passive"))
    )
    (net (code "24") (name "/L_B") (class "Default")
      (node (ref "U2") (pin "65") (pinfunction "PC8_65") (pintype "bidirectional"))
      (node (ref "U3") (pin "7") (pinfunction "HSB_7") (pintype "passive"))
    )
    (net (code "25") (name "/L_C") (class "Default")
      (node (ref "U2") (pin "64") (pinfunction "PC7_64") (pintype "bidirectional"))
      (node (ref "U3") (pin "8") (pinfunction "HSC_8") (pintype "passive"))
    )
    (net (code "26") (name "/L_ENABLE") (class "Default")
      (node (ref "U2") (pin "67") (pinfunction "PA8_67") (pintype "bidirectional"))
      (node (ref "U3") (pin "2") (pinfunction "NSLEEP_2") (pintype "input"))
      (node (ref "U3") (pin "3") (pinfunction "LSA_3") (pintype "passive"))
      (node (ref "U3") (pin "4") (pinfunction "LSB_4") (pintype "passive"))
      (node (ref "U3") (pin "5") (pinfunction "LSC_5") (pintype "passive"))
    )
    (net (code "27") (name "/L_I") (class "Default")
      (node (ref "C16") (pin "1") (pinfunction "1_1") (pintype "passive"))
      (node (ref "R7") (pin "2") (pinfunction "2_2") (pintype "passive"))
      (node (ref "U2") (pin "18") (pinfunction "PC3_18") (pintype "bidirectional"))
    )
    (net (code "28") (name "/L_SCL") (class "Default")
      (node (ref "L_ENCODER") (pin "3") (pinfunction "3_3") (pintype "passive"))
      (node (ref "R37") (pin "2") (pinfunction "2_2") (pintype "passive"))
      (node (ref "U2") (pin "61") (pinfunction "PD14_61") (pintype "bidirectional"))
    )
    (net (code "29") (name "/L_SDA") (class "Default")
      (node (ref "L_ENCODER") (pin "2") (pinfunction "2_2") (pintype "passive"))
      (node (ref "R4") (pin "2") (pinfunction "2_2") (pintype "passive"))
      (node (ref "U2") (pin "62") (pinfunction "PD15_62") (pintype "bidirectional"))
    )
    (net (code "30") (name "/L_YA") (class "Default")
      (node (ref "U$1") (pin "P$1") (pinfunction "A_P$1") (pintype "input"))
      (node (ref "U3") (pin "26") (pinfunction "SA_26") (pintype "output"))
      (node (ref "U3") (pin "9") (pinfunction "SA_2_9") (pintype "output"))
    )
    (net (code "31") (name "/L_YB") (class "Default")
      (node (ref "U$1") (pin "P$2") (pinfunction "B_P$2") (pintype "input"))
      (node (ref "U3") (pin "11") (pinfunction "SB_2_11") (pintype "output"))
      (node (ref "U3") (pin "24") (pinfunction "SB_24") (pintype "output"))
    )
    (net (code "32") (name "/L_YC") (class "Default")
      (node (ref "U$1") (pin "P$3") (pinfunction "C_P$3") (pintype "input"))
      (node (ref "U3") (pin "13") (pinfunction "SC_2_13") (pintype "output"))
      (node (ref "U3") (pin "22") (pinfunction "SC_22") (pintype "output"))
    )
    (net (code "33") (name "/MEM_SCL") (class "Default")
      (node (ref "R42") (pin "2") (pinfunction "2_2") (pintype "passive"))
      (node (ref "U$4") (pin "P$1") (pinfunction "SCL_P$1") (pintype "bidirectional"))
      (node (ref "U2") (pin "85") (pinfunction "PD4_85") (pintype "bidirectional"))
    )
    (net (code "34") (name "/MEM_SDA") (class "Default")
      (node (ref "R43") (pin "2") (pinfunction "2_2") (pintype "passive"))
      (node (ref "U$4") (pin "P$3") (pinfunction "SDA_P$3") (pintype "bidirectional"))
      (node (ref "U2") (pin "84") (pinfunction "PD3_84") (pintype "bidirectional"))
    )
    (net (code "35") (name "/OSCIN") (class "Default")
      (node (ref "C22") (pin "1") (pinfunction "1_1") (pintype "passive"))
      (node (ref "Q1") (pin "3") (pinfunction "2_3") (pintype "passive"))
      (node (ref "U2") (pin "12") (pinfunction "PH0_12") (pintype "bidirectional"))
    )
    (net (code "36") (name "/OSCOUT") (class "Default")
      (node (ref "C21") (pin "1") (pinfunction "1_1") (pintype "passive"))
      (node (ref "Q1") (pin "1") (pinfunction "1_1") (pintype "passive"))
      (node (ref "U2") (pin "13") (pinfunction "PH1_13") (pintype "bidirectional"))
    )
    (net (code "37") (name "/RESET") (class "Default")
      (node (ref "C25") (pin "2") (pinfunction "2_2") (pintype "passive"))
      (node (ref "J1") (pin "2") (pinfunction "2_2") (pintype "passive"))
      (node (ref "R15") (pin "1") (pinfunction "1_1") (pintype "passive"))
      (node (ref "RESET") (pin "3") (pinfunction "3_3") (pintype "passive"))
      (node (ref "RESET") (pin "4") (pinfunction "4_4") (pintype "passive"))
      (node (ref "U2") (pin "14") (pinfunction "NRST_14") (pintype "bidirectional"))
    )
    (net (code "38") (name "/R_A") (class "Default")
      (node (ref "U1") (pin "6") (pinfunction "HSA_6") (pintype "passive"))
      (node (ref "U2") (pin "95") (pinfunction "PB8_95") (pintype "bidirectional"))
    )
    (net (code "39") (name "/R_B") (class "Default")
      (node (ref "U1") (pin "7") (pinfunction "HSB_7") (pintype "passive"))
      (node (ref "U2") (pin "93") (pinfunction "PB7_93") (pintype "bidirectional"))
    )
    (net (code "40") (name "/R_C") (class "Default")
      (node (ref "U1") (pin "8") (pinfunction "HSC_8") (pintype "passive"))
      (node (ref "U2") (pin "92") (pinfunction "PB6_92") (pintype "bidirectional"))
    )
    (net (code "41") (name "/R_ENABLE") (class "Default")
      (node (ref "U1") (pin "2") (pinfunction "NSLEEP_2") (pintype "input"))
      (node (ref "U1") (pin "3") (pinfunction "LSA_3") (pintype "passive"))
      (node (ref "U1") (pin "4") (pinfunction "LSB_4") (pintype "passive"))
      (node (ref "U1") (pin "5") (pinfunction "LSC_5") (pintype "passive"))
      (node (ref "U2") (pin "96") (pinfunction "PB9_96") (pintype "bidirectional"))
    )
    (net (code "42") (name "/R_I") (class "Default")
      (node (ref "C20") (pin "1") (pinfunction "1_1") (pintype "passive"))
      (node (ref "R8") (pin "2") (pinfunction "2_2") (pintype "passive"))
      (node (ref "U2") (pin "17") (pinfunction "PC2_17") (pintype "bidirectional"))
    )
    (net (code "43") (name "/R_SCL") (class "Default")
      (node (ref "L_ENCODER1") (pin "3") (pinfunction "3_3") (pintype "passive"))
      (node (ref "R41") (pin "2") (pinfunction "2_2") (pintype "passive"))
      (node (ref "U2") (pin "98") (pinfunction "PE1_98") (pintype "bidirectional"))
    )
    (net (code "44") (name "/R_SDA") (class "Default")
      (node (ref "L_ENCODER1") (pin "2") (pinfunction "2_2") (pintype "passive"))
      (node (ref "R40") (pin "2") (pinfunction "2_2") (pintype "passive"))
      (node (ref "U2") (pin "97") (pinfunction "PE0_97") (pintype "bidirectional"))
    )
    (net (code "45") (name "/R_YA") (class "Default")
      (node (ref "U$2") (pin "P$3") (pinfunction "C_P$3") (pintype "input"))
      (node (ref "U1") (pin "26") (pinfunction "SA_26") (pintype "output"))
      (node (ref "U1") (pin "9") (pinfunction "SA_2_9") (pintype "output"))
    )
    (net (code "46") (name "/R_YB") (class "Default")
      (node (ref "U$2") (pin "P$2") (pinfunction "B_P$2") (pintype "input"))
      (node (ref "U1") (pin "11") (pinfunction "SB_2_11") (pintype "output"))
      (node (ref "U1") (pin "24") (pinfunction "SB_24") (pintype "output"))
    )
    (net (code "47") (name "/R_YC") (class "Default")
      (node (ref "U$2") (pin "P$1") (pinfunction "A_P$1") (pintype "input"))
      (node (ref "U1") (pin "13") (pinfunction "SC_2_13") (pintype "output"))
      (node (ref "U1") (pin "22") (pinfunction "SC_22") (pintype "output"))
    )
    (net (code "48") (name "/SCL") (class "Default")
      (node (ref "R14") (pin "1") (pinfunction "1_1") (pintype "passive"))
      (node (ref "U$3") (pin "P$13") (pinfunction "SCL_P$13") (pintype "bidirectional"))
      (node (ref "U2") (pin "83") (pinfunction "PD2_83") (pintype "bidirectional"))
    )
    (net (code "49") (name "/SDA") (class "Default")
      (node (ref "R13") (pin "1") (pinfunction "1_1") (pintype "passive"))
      (node (ref "U$3") (pin "P$14") (pinfunction "SDA_P$14") (pintype "bidirectional"))
      (node (ref "U2") (pin "82") (pinfunction "PD1_82") (pintype "bidirectional"))
    )
    (net (code "50") (name "/SWCLK") (class "Default")
      (node (ref "J1") (pin "4") (pinfunction "4_4") (pintype "passive"))
      (node (ref "U2") (pin "76") (pinfunction "PA14_76") (pintype "bidirectional"))
    )
    (net (code "51") (name "/SWDIO") (class "Default")
      (node (ref "J1") (pin "6") (pinfunction "6_6") (pintype "passive"))
      (node (ref "U2") (pin "72") (pinfunction "PA13_72") (pintype "bidirectional"))
    )
    (net (code "52") (name "/UART_RX") (class "Default")
      (node (ref "J1") (pin "3") (pinfunction "3_3") (pintype "passive"))
      (node (ref "U2") (pin "69") (pinfunction "PA10_69") (pintype "bidirectional"))
    )
    (net (code "53") (name "/UART_TX") (class "Default")
      (node (ref "J1") (pin "5") (pinfunction "5_5") (pintype "passive"))
      (node (ref "U2") (pin "68") (pinfunction "PA9_68") (pintype "bidirectional"))
    )
    (net (code "54") (name "/USBDM") (class "Default")
      (node (ref "L_ENCODER2") (pin "3") (pinfunction "3_3") (pintype "passive"))
      (node (ref "U2") (pin "70") (pinfunction "PA_11_70") (pintype "bidirectional"))
    )
    (net (code "55") (name "/USBDP") (class "Default")
      (node (ref "L_ENCODER2") (pin "2") (pinfunction "2_2") (pintype "passive"))
      (node (ref "R44") (pin "1") (pinfunction "1_1") (pintype "passive"))
      (node (ref "U2") (pin "71") (pinfunction "PA12_71") (pintype "bidirectional"))
    )
    (net (code "56") (name "/VBAT") (class "Default")
      (node (ref "U2") (pin "6") (pinfunction "VBAT_6") (pintype "power_in"))
    )
    (net (code "57") (name "GND") (class "Default")
      (node (ref "C1") (pin "2") (pinfunction "2_2") (pintype "passive"))
      (node (ref "C13") (pin "2") (pinfunction "2_2") (pintype "passive"))
      (node (ref "C15") (pin "2") (pinfunction "2_2") (pintype "passive"))
      (node (ref "C16") (pin "2") (pinfunction "2_2") (pintype "passive"))
      (node (ref "C17") (pin "1") (pinfunction "1_1") (pintype "passive"))
      (node (ref "C18") (pin "1") (pinfunction "1_1") (pintype "passive"))
      (node (ref "C19") (pin "2") (pinfunction "2_2") (pintype "passive"))
      (node (ref "C20") (pin "2") (pinfunction "2_2") (pintype "passive"))
      (node (ref "C21") (pin "2") (pinfunction "2_2") (pintype "passive"))
      (node (ref "C22") (pin "2") (pinfunction "2_2") (pintype "passive"))
      (node (ref "C23") (pin "1") (pinfunction "1_1") (pintype "passive"))
      (node (ref "C24") (pin "2") (pinfunction "2_2") (pintype "passive"))
      (node (ref "C25") (pin "1") (pinfunction "1_1") (pintype "passive"))
      (node (ref "C26") (pin "1") (pinfunction "1_1") (pintype "passive"))
      (node (ref "C27") (pin "2") (pinfunction "2_2") (pintype "passive"))
      (node (ref "C28") (pin "2") (pinfunction "2_2") (pintype "passive"))
      (node (ref "C29") (pin "2") (pinfunction "2_2") (pintype "passive"))
      (node (ref "C32") (pin "1") (pinfunction "1_1") (pintype "passive"))
      (node (ref "C33") (pin "1") (pinfunction "1_1") (pintype "passive"))
      (node (ref "C34") (pin "-") (pinfunction "-_-") (pintype "passive"))
      (node (ref "C35") (pin "2") (pinfunction "2_2") (pintype "passive"))
      (node (ref "C36") (pin "2") (pinfunction "2_2") (pintype "passive"))
      (node (ref "C37") (pin "2") (pinfunction "2_2") (pintype "passive"))
      (node (ref "C38") (pin "2") (pinfunction "2_2") (pintype "passive"))
      (node (ref "C4") (pin "-") (pinfunction "-_-") (pintype "passive"))
      (node (ref "C40") (pin "1") (pinfunction "1_1") (pintype "passive"))
      (node (ref "C41") (pin "1") (pinfunction "1_1") (pintype "passive"))
      (node (ref "C42") (pin "1") (pinfunction "1_1") (pintype "passive"))
      (node (ref "C43") (pin "1") (pinfunction "1_1") (pintype "passive"))
      (node (ref "C44") (pin "1") (pinfunction "1_1") (pintype "passive"))
      (node (ref "C5") (pin "2") (pinfunction "2_2") (pintype "passive"))
      (node (ref "C6") (pin "2") (pinfunction "2_2") (pintype "passive"))
      (node (ref "C7") (pin "2") (pinfunction "2_2") (pintype "passive"))
      (node (ref "C8") (pin "2") (pinfunction "2_2") (pintype "passive"))
      (node (ref "C9") (pin "2") (pinfunction "2_2") (pintype "passive"))
      (node (ref "IR_FRONT_S1") (pin "A") (pinfunction "A_A") (pintype "passive"))
      (node (ref "IR_FRONT_S2") (pin "A") (pinfunction "A_A") (pintype "passive"))
      (node (ref "IR_LEFT_S") (pin "A") (pinfunction "A_A") (pintype "passive"))
      (node (ref "IR_RIGHT_S") (pin "A") (pinfunction "A_A") (pintype "passive"))
      (node (ref "J1") (pin "7") (pinfunction "7_7") (pintype "passive"))
      (node (ref "J1") (pin "8") (pinfunction "8_8") (pintype "passive"))
      (node (ref "JP1") (pin "1") (pinfunction "1_1") (pintype "passive"))
      (node (ref "LED10") (pin "C") (pinfunction "C_C") (pintype "passive"))
      (node (ref "LED11") (pin "C") (pinfunction "C_C") (pintype "passive"))
      (node (ref "LED12") (pin "C") (pinfunction "C_C") (pintype "passive"))
      (node (ref "LED9") (pin "C") (pinfunction "C_C") (pintype "passive"))
      (node (ref "L_ENCODER") (pin "1") (pinfunction "1_1") (pintype "passive"))
      (node (ref "L_ENCODER1") (pin "1") (pinfunction "1_1") (pintype "passive"))
      (node (ref "L_ENCODER2") (pin "1") (pinfunction "1_1") (pintype "passive"))
      (node (ref "Q10") (pin "E") (pinfunction "E_E") (pintype "passive"))
      (node (ref "Q11") (pin "E") (pinfunction "E_E") (pintype "passive"))
      (node (ref "Q2") (pin "2") (pinfunction "S_2") (pintype "passive"))
      (node (ref "Q3") (pin "2") (pinfunction "S_2") (pintype "passive"))
      (node (ref "Q4") (pin "E") (pinfunction "E_E") (pintype "passive"))
      (node (ref "Q5") (pin "E") (pinfunction "E_E") (pintype "passive"))
      (node (ref "Q6") (pin "E") (pinfunction "E_E") (pintype "passive"))
      (node (ref "Q7") (pin "E") (pinfunction "E_E") (pintype "passive"))
      (node (ref "Q8") (pin "E") (pinfunction "E_E") (pintype "passive"))
      (node (ref "Q9") (pin "E") (pinfunction "E_E") (pintype "passive"))
      (node (ref "R1") (pin "1") (pinfunction "1_1") (pintype "passive"))
      (node (ref "R3") (pin "1") (pinfunction "1_1") (pintype "passive"))
      (node (ref "R30") (pin "1") (pinfunction "1_1") (pintype "passive"))
      (node (ref "R36") (pin "1") (pinfunction "1_1") (pintype "passive"))
      (node (ref "R39") (pin "1") (pinfunction "1_1") (pintype "passive"))
      (node (ref "RESET") (pin "1") (pinfunction "1_1") (pintype "passive"))
      (node (ref "RESET") (pin "2") (pinfunction "2_2") (pintype "passive"))
      (node (ref "U$3") (pin "P$1") (pinfunction "SDO/SA0_P$1") (pintype "bidirectional"))
      (node (ref "U$3") (pin "P$2") (pinfunction "SDX_P$2") (pintype "bidirectional"))
      (node (ref "U$3") (pin "P$3") (pinfunction "SCX_P$3") (pintype "bidirectional"))
      (node (ref "U$3") (pin "P$6") (pinfunction "GND1_P$6") (pintype "bidirectional"))
      (node (ref "U$3") (pin "P$7") (pinfunction "GND2_P$7") (pintype "bidirectional"))
      (node (ref "U$4") (pin "P$2") (pinfunction "GND_P$2") (pintype "bidirectional"))
      (node (ref "U$4") (pin "P$5") (pinfunction "WP_P$5") (pintype "bidirectional"))
      (node (ref "U1") (pin "18") (pinfunction "GND_18") (pintype "passive"))
      (node (ref "U2") (pin "10") (pinfunction "VSS_2_10") (pintype "passive"))
      (node (ref "U2") (pin "19") (pinfunction "VSSA_19") (pintype "passive"))
      (node (ref "U2") (pin "26") (pinfunction "VSS_26") (pintype "passive"))
      (node (ref "U2") (pin "49") (pinfunction "VSS_4_49") (pintype "power_in"))
      (node (ref "U2") (pin "74") (pinfunction "VSS_2_74") (pintype "passive"))
      (node (ref "U2") (pin "99") (pinfunction "VSS_99") (pintype "passive"))
      (node (ref "U3") (pin "18") (pinfunction "GND_18") (pintype "passive"))
      (node (ref "U4") (pin "4") (pinfunction "GND_4") (pintype "bidirectional"))
      (node (ref "USER") (pin "1") (pinfunction "1_1") (pintype "passive"))
      (node (ref "USER") (pin "2") (pinfunction "2_2") (pintype "passive"))
    )
    (net (code "58") (name "Net-(D1-PadA)") (class "Default")
      (node (ref "D1") (pin "A") (pinfunction "A_A") (pintype "passive"))
      (node (ref "L_ENCODER2") (pin "4") (pinfunction "4_4") (pintype "passive"))
    )
    (net (code "59") (name "Net-(IR_LEFT-PadA)") (class "Default")
      (node (ref "IR_LEFT") (pin "A") (pinfunction "A_A") (pintype "passive"))
      (node (ref "R33") (pin "1") (pinfunction "1_1") (pintype "passive"))
    )
    (net (code "60") (name "Net-(IR_RIGHT-PadA)") (class "Default")
      (node (ref "IR_RIGHT") (pin "A") (pinfunction "A_A") (pintype "passive"))
      (node (ref "R31") (pin "1") (pinfunction "1_1") (pintype "passive"))
    )
    (net (code "61") (name "Net-(IR_RIGHT1-PadA)") (class "Default")
      (node (ref "IR_RIGHT1") (pin "A") (pinfunction "A_A") (pintype "passive"))
      (node (ref "R29") (pin "1") (pinfunction "1_1") (pintype "passive"))
    )
    (net (code "62") (name "Net-(L1-1)") (class "Default")
      (node (ref "C39") (pin "1") (pinfunction "1_1") (pintype "passive"))
      (node (ref "L1") (pin "P$1") (pinfunction "1_P$1") (pintype "passive"))
      (node (ref "U4") (pin "5") (pinfunction "SW_5") (pintype "bidirectional"))
    )
    (net (code "63") (name "Net-(LED1-PadA)") (class "Default")
      (node (ref "LED1") (pin "A") (pinfunction "A_A") (pintype "passive"))
      (node (ref "R5") (pin "1") (pinfunction "1_1") (pintype "passive"))
    )
    (net (code "64") (name "Net-(LED2-PadA)") (class "Default")
      (node (ref "LED2") (pin "A") (pinfunction "A_A") (pintype "passive"))
      (node (ref "R10") (pin "1") (pinfunction "1_1") (pintype "passive"))
    )
    (net (code "65") (name "Net-(LED3-PadA)") (class "Default")
      (node (ref "LED3") (pin "A") (pinfunction "A_A") (pintype "passive"))
      (node (ref "R12") (pin "1") (pinfunction "1_1") (pintype "passive"))
    )
    (net (code "66") (name "Net-(LED4-PadA)") (class "Default")
      (node (ref "LED4") (pin "A") (pinfunction "A_A") (pintype "passive"))
      (node (ref "R17") (pin "1") (pinfunction "1_1") (pintype "passive"))
    )
    (net (code "67") (name "Net-(LED5-PadA)") (class "Default")
      (node (ref "LED5") (pin "A") (pinfunction "A_A") (pintype "passive"))
      (node (ref "R19") (pin "1") (pinfunction "1_1") (pintype "passive"))
    )
    (net (code "68") (name "Net-(LED6-PadA)") (class "Default")
      (node (ref "LED6") (pin "A") (pinfunction "A_A") (pintype "passive"))
      (node (ref "R21") (pin "1") (pinfunction "1_1") (pintype "passive"))
    )
    (net (code "69") (name "Net-(LED7-PadA)") (class "Default")
      (node (ref "LED7") (pin "A") (pinfunction "A_A") (pintype "passive"))
      (node (ref "R23") (pin "1") (pinfunction "1_1") (pintype "passive"))
    )
    (net (code "70") (name "Net-(LED8-PadA)") (class "Default")
      (node (ref "LED8") (pin "A") (pinfunction "A_A") (pintype "passive"))
      (node (ref "R25") (pin "1") (pinfunction "1_1") (pintype "passive"))
    )
    (net (code "71") (name "Net-(LED9-PadA)") (class "Default")
      (node (ref "LED9") (pin "A") (pinfunction "A_A") (pintype "passive"))
      (node (ref "R9") (pin "1") (pinfunction "1_1") (pintype "passive"))
    )
    (net (code "72") (name "Net-(LED10-PadA)") (class "Default")
      (node (ref "LED10") (pin "A") (pinfunction "A_A") (pintype "passive"))
      (node (ref "R38") (pin "1") (pinfunction "1_1") (pintype "passive"))
    )
    (net (code "73") (name "Net-(LED11-PadA)") (class "Default")
      (node (ref "LED11") (pin "A") (pinfunction "A_A") (pintype "passive"))
      (node (ref "R28") (pin "1") (pinfunction "1_1") (pintype "passive"))
    )
    (net (code "74") (name "Net-(LED12-PadA)") (class "Default")
      (node (ref "LED12") (pin "A") (pinfunction "A_A") (pintype "passive"))
      (node (ref "R27") (pin "2") (pinfunction "2_2") (pintype "passive"))
    )
    (net (code "75") (name "Net-(U1-CP1)") (class "Default")
      (node (ref "C2") (pin "2") (pinfunction "2_2") (pintype "passive"))
      (node (ref "U1") (pin "20") (pinfunction "CP1_20") (pintype "passive"))
    )
    (net (code "76") (name "Net-(U1-CP2)") (class "Default")
      (node (ref "C2") (pin "1") (pinfunction "1_1") (pintype "passive"))
      (node (ref "U1") (pin "21") (pinfunction "CP2_21") (pintype "passive"))
    )
    (net (code "77") (name "Net-(U1-LSS)") (class "Default")
      (node (ref "R1") (pin "2") (pinfunction "2_2") (pintype "passive"))
      (node (ref "R8") (pin "1") (pinfunction "1_1") (pintype "passive"))
      (node (ref "U1") (pin "10") (pinfunction "LSS_2_10") (pintype "passive"))
      (node (ref "U1") (pin "12") (pinfunction "LSS_12") (pintype "passive"))
    )
    (net (code "78") (name "Net-(U1-VCP)") (class "Default")
      (node (ref "C3") (pin "1") (pinfunction "1_1") (pintype "passive"))
      (node (ref "U1") (pin "19") (pinfunction "VCP_19") (pintype "output"))
    )
    (net (code "79") (name "Net-(U1-VG)") (class "Default")
      (node (ref "C1") (pin "1") (pinfunction "1_1") (pintype "passive"))
      (node (ref "U1") (pin "14") (pinfunction "VG_14") (pintype "power_in"))
    )
    (net (code "80") (name "Net-(U2A-VCAP_1)") (class "Default")
      (node (ref "C23") (pin "2") (pinfunction "2_2") (pintype "passive"))
      (node (ref "U2") (pin "48") (pinfunction "VCAP_1_48") (pintype "power_in"))
    )
    (net (code "81") (name "Net-(U2B-VCAP_2)") (class "Default")
      (node (ref "C19") (pin "1") (pinfunction "1_1") (pintype "passive"))
      (node (ref "U2") (pin "73") (pinfunction "VCAP_2_73") (pintype "power_in"))
    )
    (net (code "82") (name "Net-(U3-CP1)") (class "Default")
      (node (ref "C30") (pin "2") (pinfunction "2_2") (pintype "passive"))
      (node (ref "U3") (pin "20") (pinfunction "CP1_20") (pintype "passive"))
    )
    (net (code "83") (name "Net-(U3-CP2)") (class "Default")
      (node (ref "C30") (pin "1") (pinfunction "1_1") (pintype "passive"))
      (node (ref "U3") (pin "21") (pinfunction "CP2_21") (pintype "passive"))
    )
    (net (code "84") (name "Net-(U3-LSS)") (class "Default")
      (node (ref "R36") (pin "2") (pinfunction "2_2") (pintype "passive"))
      (node (ref "R7") (pin "1") (pinfunction "1_1") (pintype "passive"))
      (node (ref "U3") (pin "10") (pinfunction "LSS_2_10") (pintype "passive"))
      (node (ref "U3") (pin "12") (pinfunction "LSS_12") (pintype "passive"))
    )
    (net (code "85") (name "Net-(U3-VCP)") (class "Default")
      (node (ref "C31") (pin "1") (pinfunction "1_1") (pintype "passive"))
      (node (ref "U3") (pin "19") (pinfunction "VCP_19") (pintype "output"))
    )
    (net (code "86") (name "Net-(U3-VG)") (class "Default")
      (node (ref "C13") (pin "1") (pinfunction "1_1") (pintype "passive"))
      (node (ref "U3") (pin "14") (pinfunction "VG_14") (pintype "power_in"))
    )
    (net (code "87") (name "Net-(U4-BST)") (class "Default")
      (node (ref "C39") (pin "2") (pinfunction "2_2") (pintype "passive"))
      (node (ref "U4") (pin "6") (pinfunction "BST_6") (pintype "bidirectional"))
    )
    (net (code "88") (name "VCC") (class "Default")
      (node (ref "C17") (pin "2") (pinfunction "2_2") (pintype "passive"))
      (node (ref "C18") (pin "2") (pinfunction "2_2") (pintype "passive"))
      (node (ref "C3") (pin "2") (pinfunction "2_2") (pintype "passive"))
      (node (ref "C31") (pin "2") (pinfunction "2_2") (pintype "passive"))
      (node (ref "C32") (pin "2") (pinfunction "2_2") (pintype "passive"))
      (node (ref "C33") (pin "2") (pinfunction "2_2") (pintype "passive"))
      (node (ref "C34") (pin "+") (pinfunction "+_+") (pintype "passive"))
      (node (ref "C4") (pin "+") (pinfunction "+_+") (pintype "passive"))
      (node (ref "C40") (pin "2") (pinfunction "2_2") (pintype "passive"))
      (node (ref "C41") (pin "2") (pinfunction "2_2") (pintype "passive"))
      (node (ref "D1") (pin "C") (pinfunction "C_C") (pintype "passive"))
      (node (ref "JP1") (pin "2") (pinfunction "2_2") (pintype "passive"))
      (node (ref "U1") (pin "23") (pinfunction "VIN_2_23") (pintype "power_in"))
      (node (ref "U1") (pin "25") (pinfunction "VIN_25") (pintype "power_in"))
      (node (ref "U3") (pin "23") (pinfunction "VIN_2_23") (pintype "power_in"))
      (node (ref "U3") (pin "25") (pinfunction "VIN_25") (pintype "power_in"))
      (node (ref "U4") (pin "2") (pinfunction "EN_2") (pintype "bidirectional"))
      (node (ref "U4") (pin "3") (pinfunction "VIN_3") (pintype "bidirectional"))
    )
    (net (code "89") (name "unconnected-(U$3-INT1-PadP$4)") (class "Default")
      (node (ref "U$3") (pin "P$4") (pinfunction "INT1_P$4") (pintype "bidirectional"))
    )
    (net (code "90") (name "unconnected-(U$3-INT2-PadP$9)") (class "Default")
      (node (ref "U$3") (pin "P$9") (pinfunction "INT2_P$9") (pintype "bidirectional"))
    )
    (net (code "91") (name "unconnected-(U$3-NC1-PadP$10)") (class "Default")
      (node (ref "U$3") (pin "P$10") (pinfunction "NC1_P$10") (pintype "bidirectional"))
    )
    (net (code "92") (name "unconnected-(U$3-NC2-PadP$11)") (class "Default")
      (node (ref "U$3") (pin "P$11") (pinfunction "NC2_P$11") (pintype "bidirectional"))
    )
    (net (code "93") (name "unconnected-(U1-NFAULT-Pad1)") (class "Default")
      (node (ref "U1") (pin "1") (pinfunction "NFAULT_1") (pintype "output"))
    )
    (net (code "94") (name "unconnected-(U1-SOA-Pad15)") (class "Default")
      (node (ref "U1") (pin "15") (pinfunction "SOA_15") (pintype "output"))
    )
    (net (code "95") (name "unconnected-(U1-SOB-Pad16)") (class "Default")
      (node (ref "U1") (pin "16") (pinfunction "SOB_16") (pintype "output"))
    )
    (net (code "96") (name "unconnected-(U1-SOC-Pad17)") (class "Default")
      (node (ref "U1") (pin "17") (pinfunction "SOC_17") (pintype "output"))
    )
    (net (code "97") (name "unconnected-(U2A-PB2-Pad36)") (class "Default")
      (node (ref "U2") (pin "36") (pinfunction "PB2_36") (pintype "bidirectional"))
    )
    (net (code "98") (name "unconnected-(U2A-PB10-Pad46)") (class "Default")
      (node (ref "U2") (pin "46") (pinfunction "PB10_46") (pintype "bidirectional"))
    )
    (net (code "99") (name "unconnected-(U2A-PB11-Pad47)") (class "Default")
      (node (ref "U2") (pin "47") (pinfunction "PB11_47") (pintype "bidirectional"))
    )
    (net (code "100") (name "unconnected-(U2A-PC0-Pad15)") (class "Default")
      (node (ref "U2") (pin "15") (pinfunction "PC0_15") (pintype "bidirectional"))
    )
    (net (code "101") (name "unconnected-(U2A-PC1-Pad16)") (class "Default")
      (node (ref "U2") (pin "16") (pinfunction "PC1_16") (pintype "bidirectional"))
    )
    (net (code "102") (name "unconnected-(U2A-PC13-Pad7)") (class "Default")
      (node (ref "U2") (pin "7") (pinfunction "PC13_7") (pintype "bidirectional"))
    )
    (net (code "103") (name "unconnected-(U2A-PE5-Pad4)") (class "Default")
      (node (ref "U2") (pin "4") (pinfunction "PE5_4") (pintype "bidirectional"))
    )
    (net (code "104") (name "unconnected-(U2A-PE6-Pad5)") (class "Default")
      (node (ref "U2") (pin "5") (pinfunction "PE6_5") (pintype "bidirectional"))
    )
    (net (code "105") (name "unconnected-(U2A-PE7-Pad37)") (class "Default")
      (node (ref "U2") (pin "37") (pinfunction "PE7_37") (pintype "bidirectional"))
    )
    (net (code "106") (name "unconnected-(U2A-PE8-Pad38)") (class "Default")
      (node (ref "U2") (pin "38") (pinfunction "PE8_38") (pintype "bidirectional"))
    )
    (net (code "107") (name "unconnected-(U2A-PE9-Pad39)") (class "Default")
      (node (ref "U2") (pin "39") (pinfunction "PE9_39") (pintype "bidirectional"))
    )
    (net (code "108") (name "unconnected-(U2A-PE10-Pad40)") (class "Default")
      (node (ref "U2") (pin "40") (pinfunction "PE10_40") (pintype "bidirectional"))
    )
    (net (code "109") (name "unconnected-(U2A-PE11-Pad41)") (class "Default")
      (node (ref "U2") (pin "41") (pinfunction "PE11_41") (pintype "bidirectional"))
    )
    (net (code "110") (name "unconnected-(U2A-PE12-Pad42)") (class "Default")
      (node (ref "U2") (pin "42") (pinfunction "PE12_42") (pintype "bidirectional"))
    )
    (net (code "111") (name "unconnected-(U2A-PE13-Pad43)") (class "Default")
      (node (ref "U2") (pin "43") (pinfunction "PE13_43") (pintype "bidirectional"))
    )
    (net (code "112") (name "unconnected-(U2A-PE14-Pad44)") (class "Default")
      (node (ref "U2") (pin "44") (pinfunction "PE14_44") (pintype "bidirectional"))
    )
    (net (code "113") (name "unconnected-(U2A-PE15-Pad45)") (class "Default")
      (node (ref "U2") (pin "45") (pinfunction "PE15_45") (pintype "bidirectional"))
    )
    (net (code "114") (name "unconnected-(U2B-PA15-Pad77)") (class "Default")
      (node (ref "U2") (pin "77") (pinfunction "PA15_77") (pintype "bidirectional"))
    )
    (net (code "115") (name "unconnected-(U2B-PB3-Pad89)") (class "Default")
      (node (ref "U2") (pin "89") (pinfunction "PB3_89") (pintype "bidirectional"))
    )
    (net (code "116") (name "unconnected-(U2B-PB4-Pad90)") (class "Default")
      (node (ref "U2") (pin "90") (pinfunction "PB4_90") (pintype "bidirectional"))
    )
    (net (code "117") (name "unconnected-(U2B-PB5-Pad91)") (class "Default")
      (node (ref "U2") (pin "91") (pinfunction "PB5_91") (pintype "bidirectional"))
    )
    (net (code "118") (name "unconnected-(U2B-PB12-Pad51)") (class "Default")
      (node (ref "U2") (pin "51") (pinfunction "PB12_51") (pintype "bidirectional"))
    )
    (net (code "119") (name "unconnected-(U2B-PB13-Pad52)") (class "Default")
      (node (ref "U2") (pin "52") (pinfunction "PB13_52") (pintype "bidirectional"))
    )
    (net (code "120") (name "unconnected-(U2B-PB14-Pad53)") (class "Default")
      (node (ref "U2") (pin "53") (pinfunction "PB14_53") (pintype "bidirectional"))
    )
    (net (code "121") (name "unconnected-(U2B-PB15-Pad54)") (class "Default")
      (node (ref "U2") (pin "54") (pinfunction "PB15_54") (pintype "bidirectional"))
    )
    (net (code "122") (name "unconnected-(U2B-PC6-Pad63)") (class "Default")
      (node (ref "U2") (pin "63") (pinfunction "PC6_63") (pintype "bidirectional"))
    )
    (net (code "123") (name "unconnected-(U2B-PC10-Pad78)") (class "Default")
      (node (ref "U2") (pin "78") (pinfunction "PC10_78") (pintype "bidirectional"))
    )
    (net (code "124") (name "unconnected-(U2B-PC11-Pad79)") (class "Default")
      (node (ref "U2") (pin "79") (pinfunction "PC11_79") (pintype "bidirectional"))
    )
    (net (code "125") (name "unconnected-(U2B-PC12-Pad80)") (class "Default")
      (node (ref "U2") (pin "80") (pinfunction "PC12_80") (pintype "bidirectional"))
    )
    (net (code "126") (name "unconnected-(U2B-PD0-Pad81)") (class "Default")
      (node (ref "U2") (pin "81") (pinfunction "PD0_81") (pintype "bidirectional"))
    )
    (net (code "127") (name "unconnected-(U2B-PD5-Pad86)") (class "Default")
      (node (ref "U2") (pin "86") (pinfunction "PD5_86") (pintype "bidirectional"))
    )
    (net (code "128") (name "unconnected-(U2B-PD6-Pad87)") (class "Default")
      (node (ref "U2") (pin "87") (pinfunction "PD6_87") (pintype "bidirectional"))
    )
    (net (code "129") (name "unconnected-(U2B-PD7-Pad88)") (class "Default")
      (node (ref "U2") (pin "88") (pinfunction "PD7_88") (pintype "bidirectional"))
    )
    (net (code "130") (name "unconnected-(U2B-PD8-Pad55)") (class "Default")
      (node (ref "U2") (pin "55") (pinfunction "PD8_55") (pintype "bidirectional"))
    )
    (net (code "131") (name "unconnected-(U2B-PD9-Pad56)") (class "Default")
      (node (ref "U2") (pin "56") (pinfunction "PD9_56") (pintype "bidirectional"))
    )
    (net (code "132") (name "unconnected-(U2B-PD10-Pad57)") (class "Default")
      (node (ref "U2") (pin "57") (pinfunction "PD10_57") (pintype "bidirectional"))
    )
    (net (code "133") (name "unconnected-(U2B-PD11-Pad58)") (class "Default")
      (node (ref "U2") (pin "58") (pinfunction "PD11_58") (pintype "bidirectional"))
    )
    (net (code "134") (name "unconnected-(U2B-PD12-Pad59)") (class "Default")
      (node (ref "U2") (pin "59") (pinfunction "PD12_59") (pintype "bidirectional"))
    )
    (net (code "135") (name "unconnected-(U3-NFAULT-Pad1)") (class "Default")
      (node (ref "U3") (pin "1") (pinfunction "NFAULT_1") (pintype "output"))
    )
    (net (code "136") (name "unconnected-(U3-SOA-Pad15)") (class "Default")
      (node (ref "U3") (pin "15") (pinfunction "SOA_15") (pintype "output"))
    )
    (net (code "137") (name "unconnected-(U3-SOB-Pad16)") (class "Default")
      (node (ref "U3") (pin "16") (pinfunction "SOB_16") (pintype "output"))
    )
    (net (code "138") (name "unconnected-(U3-SOC-Pad17)") (class "Default")
      (node (ref "U3") (pin "17") (pinfunction "SOC_17") (pintype "output"))
    )
    (net (code "139") (name "unconnected-(USER-Pad3)") (class "Default")
      (node (ref "USER") (pin "3") (pinfunction "3_3") (pintype "passive"))
    )
  )
)
